# dimmer.net
KiCad netlist of a schematic drawn in EAGLE
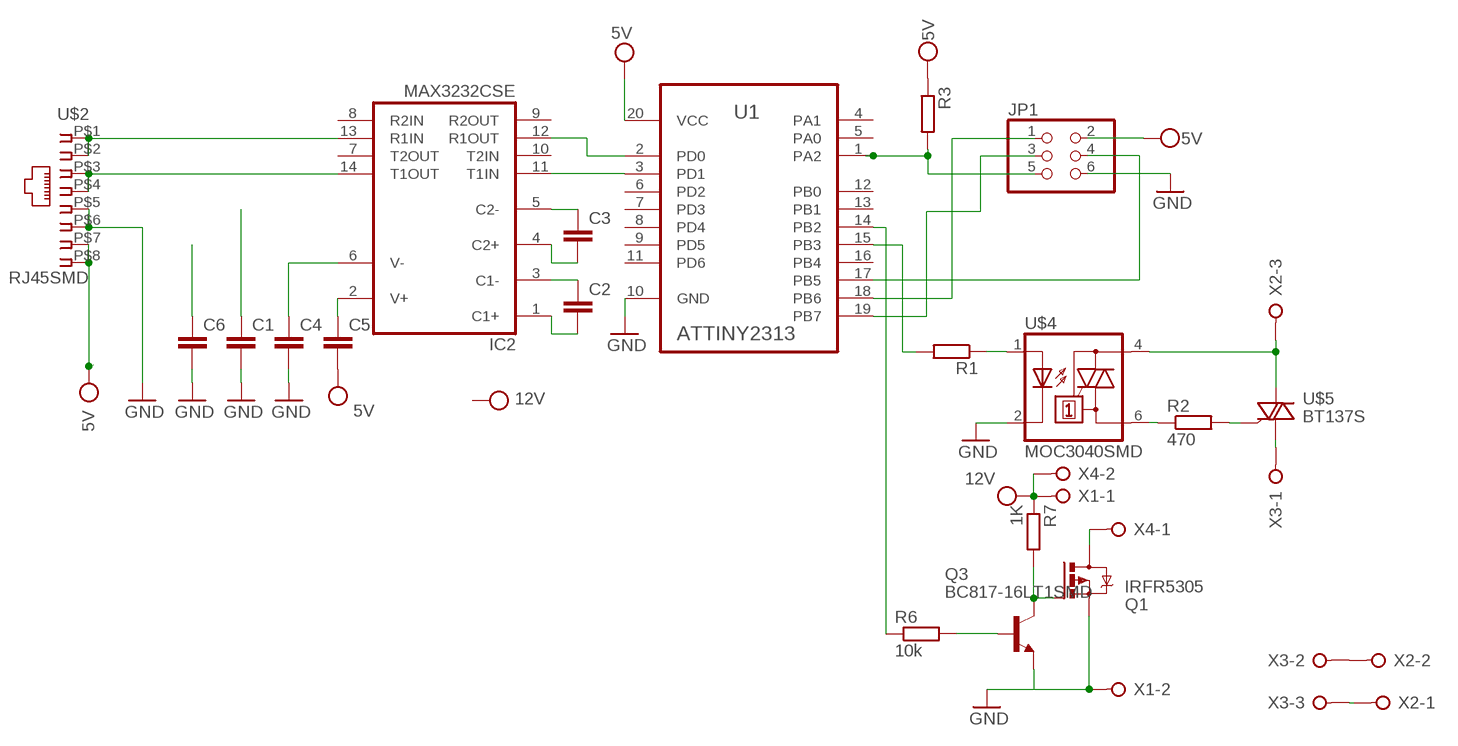
[diagram p0: schematic, sheet 1]

(export (version "E")
  (design (tool "Eeschema 10.0.6"))
  (components
    (comp (ref "C1")
      (value "C-EUC1206")
      (footprint "eagle-import:C1206")
      (libsource (lib "eagle-import") (part "C-EUC1206"))
    )
    (comp (ref "C2")
      (value "C-EUC0603")
      (footprint "eagle-import:C0603")
      (libsource (lib "eagle-import") (part "C-EUC0603"))
    )
    (comp (ref "C3")
      (value "C-EUC0603")
      (footprint "eagle-import:C0603")
      (libsource (lib "eagle-import") (part "C-EUC0603"))
    )
    (comp (ref "C4")
      (value "C-EUC0603")
      (footprint "eagle-import:C0603")
      (libsource (lib "eagle-import") (part "C-EUC0603"))
    )
    (comp (ref "C5")
      (value "C-EUC0603")
      (footprint "eagle-import:C0603")
      (libsource (lib "eagle-import") (part "C-EUC0603"))
    )
    (comp (ref "C6")
      (value "C-EUC1206")
      (footprint "eagle-import:C1206")
      (libsource (lib "eagle-import") (part "C-EUC1206"))
    )
    (comp (ref "IC2")
      (value "MAX3232CSE")
      (footprint "eagle-import:SO16")
      (libsource (lib "eagle-import") (part "MAX3232SEC"))
    )
    (comp (ref "JP1")
      (value "PINHD-2X3")
      (footprint "eagle-import:2X03")
      (libsource (lib "eagle-import") (part "PINHD-2X3"))
    )
    (comp (ref "Q1")
      (value "IRFR5305")
      (footprint "eagle-import:D-PAK_TO252AA")
      (libsource (lib "eagle-import") (part "IRF?5305R"))
    )
    (comp (ref "Q3")
      (value "BC817-16LT1SMD")
      (footprint "eagle-import:SOT23-BEC")
      (libsource (lib "eagle-import") (part "BC817SMD-16LT1"))
    )
    (comp (ref "R1")
      (value "R-EU_R1206")
      (footprint "eagle-import:R1206")
      (libsource (lib "eagle-import") (part "R-EU_R1206"))
    )
    (comp (ref "R2")
      (value "470")
      (footprint "eagle-import:R1206")
      (libsource (lib "eagle-import") (part "R-EU_R1206"))
    )
    (comp (ref "R3")
      (value "R-EU_R1206")
      (footprint "eagle-import:R1206")
      (libsource (lib "eagle-import") (part "R-EU_R1206"))
    )
    (comp (ref "R6")
      (value "10k")
      (footprint "eagle-import:R1206")
      (libsource (lib "eagle-import") (part "R-EU_R1206"))
    )
    (comp (ref "R7")
      (value "1K")
      (footprint "eagle-import:R1206")
      (libsource (lib "eagle-import") (part "R-EU_R1206"))
    )
    (comp (ref "U$2")
      (value "RJ45SMD")
      (footprint "eagle-import:RJ45SMD")
      (libsource (lib "eagle-import") (part "RJ45SMD"))
    )
    (comp (ref "U$4")
      (value "MOC3040SMD")
      (footprint "eagle-import:DIL6-SMD")
      (libsource (lib "eagle-import") (part "MOC3040SMD"))
    )
    (comp (ref "U$5")
      (value "BT137S")
      (footprint "eagle-import:DPACK")
      (libsource (lib "eagle-import") (part "BT137S"))
    )
    (comp (ref "U1")
      (value "ATTINY2313")
      (footprint "eagle-import:SOIC127P1032X265-20N")
      (fields (field (name "MPN") "ATTINY2313-20SU"))
      (libsource (lib "eagle-import") (part "ATTINY2313-20SU"))
    )
    (comp (ref "X1")
      (value "W237-02P")
      (footprint "eagle-import:W237-132")
      (libsource (lib "eagle-import") (part "W237-02P"))
    )
    (comp (ref "X2")
      (value "W237-3E")
      (footprint "eagle-import:W237-3E")
      (libsource (lib "eagle-import") (part "W237-3E"))
    )
    (comp (ref "X3")
      (value "W237-3E")
      (footprint "eagle-import:W237-3E")
      (libsource (lib "eagle-import") (part "W237-3E"))
    )
    (comp (ref "X4")
      (value "W237-02P")
      (footprint "eagle-import:W237-132")
      (libsource (lib "eagle-import") (part "W237-02P"))
    )
  )
  (nets
    (net (code "1") (name "5V") (class "Default")
      (node (ref "C1") (pin "1") (pinfunction "1_1") (pintype "passive"))
      (node (ref "C5") (pin "2") (pinfunction "2_2") (pintype "passive"))
      (node (ref "JP1") (pin "2") (pinfunction "2_2") (pintype "passive"))
      (node (ref "R3") (pin "1") (pinfunction "1_1") (pintype "passive"))
      (node (ref "U$2") (pin "P$7") (pinfunction "7_P$7") (pintype "passive"))
      (node (ref "U$2") (pin "P$8") (pinfunction "8_P$8") (pintype "passive"))
      (node (ref "U1") (pin "20") (pinfunction "VCC_20") (pintype "power_in"))
    )
    (net (code "2") (name "12V") (class "Default")
      (node (ref "C6") (pin "1") (pinfunction "1_1") (pintype "passive"))
      (node (ref "R7") (pin "1") (pinfunction "1_1") (pintype "passive"))
      (node (ref "X1") (pin "1") (pinfunction "KL_1") (pintype "passive"))
      (node (ref "X4") (pin "2") (pinfunction "KL_2") (pintype "passive"))
    )
    (net (code "3") (name "GND") (class "Default")
      (node (ref "C1") (pin "2") (pinfunction "2_2") (pintype "passive"))
      (node (ref "C4") (pin "2") (pinfunction "2_2") (pintype "passive"))
      (node (ref "C6") (pin "2") (pinfunction "2_2") (pintype "passive"))
      (node (ref "JP1") (pin "6") (pinfunction "6_6") (pintype "passive"))
      (node (ref "Q1") (pin "3") (pinfunction "S_3") (pintype "passive"))
      (node (ref "Q3") (pin "E") (pinfunction "E_E") (pintype "passive"))
      (node (ref "U$2") (pin "P$5") (pinfunction "5_P$5") (pintype "passive"))
      (node (ref "U$2") (pin "P$6") (pinfunction "6_P$6") (pintype "passive"))
      (node (ref "U$4") (pin "2") (pinfunction "C_2") (pintype "passive"))
      (node (ref "U1") (pin "10") (pinfunction "GND_10") (pintype "passive"))
      (node (ref "X1") (pin "2") (pinfunction "KL_2") (pintype "passive"))
    )
    (net (code "4") (name "Net-(IC2A-C1+)") (class "Default")
      (node (ref "C2") (pin "2") (pinfunction "2_2") (pintype "passive"))
      (node (ref "IC2") (pin "1") (pinfunction "C1+_1") (pintype "bidirectional"))
    )
    (net (code "5") (name "Net-(IC2A-C1-)") (class "Default")
      (node (ref "C2") (pin "1") (pinfunction "1_1") (pintype "passive"))
      (node (ref "IC2") (pin "3") (pinfunction "C1-_3") (pintype "bidirectional"))
    )
    (net (code "6") (name "Net-(IC2A-C2+)") (class "Default")
      (node (ref "C3") (pin "2") (pinfunction "2_2") (pintype "passive"))
      (node (ref "IC2") (pin "4") (pinfunction "C2+_4") (pintype "bidirectional"))
    )
    (net (code "7") (name "Net-(IC2A-C2-)") (class "Default")
      (node (ref "C3") (pin "1") (pinfunction "1_1") (pintype "passive"))
      (node (ref "IC2") (pin "5") (pinfunction "C2-_5") (pintype "bidirectional"))
    )
    (net (code "8") (name "Net-(IC2A-R1IN)") (class "Default")
      (node (ref "IC2") (pin "13") (pinfunction "R1IN_13") (pintype "input"))
      (node (ref "U$2") (pin "P$1") (pinfunction "1_P$1") (pintype "passive"))
      (node (ref "U$2") (pin "P$2") (pinfunction "2_P$2") (pintype "passive"))
    )
    (net (code "9") (name "Net-(IC2A-R1OUT)") (class "Default")
      (node (ref "IC2") (pin "12") (pinfunction "R1OUT_12") (pintype "output"))
      (node (ref "U1") (pin "2") (pinfunction "PD0_2") (pintype "bidirectional"))
    )
    (net (code "10") (name "Net-(IC2A-T1IN)") (class "Default")
      (node (ref "IC2") (pin "11") (pinfunction "T1IN_11") (pintype "input"))
      (node (ref "U1") (pin "3") (pinfunction "PD1_3") (pintype "bidirectional"))
    )
    (net (code "11") (name "Net-(IC2A-T1OUT)") (class "Default")
      (node (ref "IC2") (pin "14") (pinfunction "T1OUT_14") (pintype "output"))
      (node (ref "U$2") (pin "P$3") (pinfunction "3_P$3") (pintype "passive"))
      (node (ref "U$2") (pin "P$4") (pinfunction "4_P$4") (pintype "passive"))
    )
    (net (code "12") (name "Net-(IC2A-V+)") (class "Default")
      (node (ref "C5") (pin "1") (pinfunction "1_1") (pintype "passive"))
      (node (ref "IC2") (pin "2") (pinfunction "V+_2") (pintype "bidirectional"))
    )
    (net (code "13") (name "Net-(IC2A-V-)") (class "Default")
      (node (ref "C4") (pin "1") (pinfunction "1_1") (pintype "passive"))
      (node (ref "IC2") (pin "6") (pinfunction "V-_6") (pintype "bidirectional"))
    )
    (net (code "14") (name "Net-(Q1-D)") (class "Default")
      (node (ref "Q1") (pin "4") (pinfunction "D_4") (pintype "passive"))
      (node (ref "X4") (pin "1") (pinfunction "KL_1") (pintype "passive"))
    )
    (net (code "15") (name "Net-(Q1-G)") (class "Default")
      (node (ref "Q1") (pin "1") (pinfunction "G_1") (pintype "passive"))
      (node (ref "Q3") (pin "C") (pinfunction "C_C") (pintype "passive"))
      (node (ref "R7") (pin "2") (pinfunction "2_2") (pintype "passive"))
    )
    (net (code "16") (name "Net-(Q3-PadB)") (class "Default")
      (node (ref "Q3") (pin "B") (pinfunction "B_B") (pintype "passive"))
      (node (ref "R6") (pin "2") (pinfunction "2_2") (pintype "passive"))
    )
    (net (code "17") (name "Net-(U$4-A)") (class "Default")
      (node (ref "R1") (pin "1") (pinfunction "1_1") (pintype "passive"))
      (node (ref "U$4") (pin "1") (pinfunction "A_1") (pintype "passive"))
    )
    (net (code "18") (name "Net-(U$4-A1)") (class "Default")
      (node (ref "R2") (pin "1") (pinfunction "1_1") (pintype "passive"))
      (node (ref "U$4") (pin "6") (pinfunction "A1_6") (pintype "passive"))
    )
    (net (code "19") (name "Net-(U$4-A2)") (class "Default")
      (node (ref "U$4") (pin "4") (pinfunction "A2_4") (pintype "passive"))
      (node (ref "U$5") (pin "2") (pinfunction "A2_2") (pintype "passive"))
      (node (ref "X2") (pin "3") (pinfunction "KL_3") (pintype "passive"))
    )
    (net (code "20") (name "Net-(U$5-A1)") (class "Default")
      (node (ref "U$5") (pin "1") (pinfunction "A1_1") (pintype "passive"))
      (node (ref "X3") (pin "1") (pinfunction "KL_1") (pintype "passive"))
    )
    (net (code "21") (name "Net-(U$5-G)") (class "Default")
      (node (ref "R2") (pin "2") (pinfunction "2_2") (pintype "passive"))
      (node (ref "U$5") (pin "3") (pinfunction "G_3") (pintype "passive"))
    )
    (net (code "22") (name "Net-(U1-PA2)") (class "Default")
      (node (ref "JP1") (pin "5") (pinfunction "5_5") (pintype "passive"))
      (node (ref "R3") (pin "2") (pinfunction "2_2") (pintype "passive"))
      (node (ref "U1") (pin "1") (pinfunction "PA2_1") (pintype "bidirectional"))
    )
    (net (code "23") (name "Net-(U1-PB2)") (class "Default")
      (node (ref "R6") (pin "1") (pinfunction "1_1") (pintype "passive"))
      (node (ref "U1") (pin "14") (pinfunction "PB2_14") (pintype "bidirectional"))
    )
    (net (code "24") (name "Net-(U1-PB3)") (class "Default")
      (node (ref "R1") (pin "2") (pinfunction "2_2") (pintype "passive"))
      (node (ref "U1") (pin "15") (pinfunction "PB3_15") (pintype "bidirectional"))
    )
    (net (code "25") (name "Net-(U1-PB5)") (class "Default")
      (node (ref "JP1") (pin "4") (pinfunction "4_4") (pintype "passive"))
      (node (ref "U1") (pin "17") (pinfunction "PB5_17") (pintype "bidirectional"))
    )
    (net (code "26") (name "Net-(U1-PB6)") (class "Default")
      (node (ref "JP1") (pin "1") (pinfunction "1_1") (pintype "passive"))
      (node (ref "U1") (pin "18") (pinfunction "PB6_18") (pintype "bidirectional"))
    )
    (net (code "27") (name "Net-(U1-PB7)") (class "Default")
      (node (ref "JP1") (pin "3") (pinfunction "3_3") (pintype "passive"))
      (node (ref "U1") (pin "19") (pinfunction "PB7_19") (pintype "bidirectional"))
    )
    (net (code "28") (name "Net-(X2A-KL)") (class "Default")
      (node (ref "X2") (pin "1") (pinfunction "KL_1") (pintype "passive"))
      (node (ref "X3") (pin "3") (pinfunction "KL_3") (pintype "passive"))
    )
    (net (code "29") (name "Net-(X2B-KL)") (class "Default")
      (node (ref "X2") (pin "2") (pinfunction "KL_2") (pintype "passive"))
      (node (ref "X3") (pin "2") (pinfunction "KL_2") (pintype "passive"))
    )
    (net (code "30") (name "unconnected-(IC2A-R2IN-Pad8)") (class "Default")
      (node (ref "IC2") (pin "8") (pinfunction "R2IN_8") (pintype "input"))
    )
    (net (code "31") (name "unconnected-(IC2A-R2OUT-Pad9)") (class "Default")
      (node (ref "IC2") (pin "9") (pinfunction "R2OUT_9") (pintype "output"))
    )
    (net (code "32") (name "unconnected-(IC2A-T2IN-Pad10)") (class "Default")
      (node (ref "IC2") (pin "10") (pinfunction "T2IN_10") (pintype "input"))
    )
    (net (code "33") (name "unconnected-(IC2A-T2OUT-Pad7)") (class "Default")
      (node (ref "IC2") (pin "7") (pinfunction "T2OUT_7") (pintype "output"))
    )
    (net (code "34") (name "unconnected-(U1-PA0-Pad5)") (class "Default")
      (node (ref "U1") (pin "5") (pinfunction "PA0_5") (pintype "bidirectional"))
    )
    (net (code "35") (name "unconnected-(U1-PA1-Pad4)") (class "Default")
      (node (ref "U1") (pin "4") (pinfunction "PA1_4") (pintype "bidirectional"))
    )
    (net (code "36") (name "unconnected-(U1-PB0-Pad12)") (class "Default")
      (node (ref "U1") (pin "12") (pinfunction "PB0_12") (pintype "bidirectional"))
    )
    (net (code "37") (name "unconnected-(U1-PB1-Pad13)") (class "Default")
      (node (ref "U1") (pin "13") (pinfunction "PB1_13") (pintype "bidirectional"))
    )
    (net (code "38") (name "unconnected-(U1-PB4-Pad16)") (class "Default")
      (node (ref "U1") (pin "16") (pinfunction "PB4_16") (pintype "bidirectional"))
    )
    (net (code "39") (name "unconnected-(U1-PD2-Pad6)") (class "Default")
      (node (ref "U1") (pin "6") (pinfunction "PD2_6") (pintype "bidirectional"))
    )
    (net (code "40") (name "unconnected-(U1-PD3-Pad7)") (class "Default")
      (node (ref "U1") (pin "7") (pinfunction "PD3_7") (pintype "bidirectional"))
    )
    (net (code "41") (name "unconnected-(U1-PD4-Pad8)") (class "Default")
      (node (ref "U1") (pin "8") (pinfunction "PD4_8") (pintype "bidirectional"))
    )
    (net (code "42") (name "unconnected-(U1-PD5-Pad9)") (class "Default")
      (node (ref "U1") (pin "9") (pinfunction "PD5_9") (pintype "bidirectional"))
    )
    (net (code "43") (name "unconnected-(U1-PD6-Pad11)") (class "Default")
      (node (ref "U1") (pin "11") (pinfunction "PD6_11") (pintype "bidirectional"))
    )
  )
)
